# TPS65133_SingleChannel.net
KiCad netlist of a schematic drawn in Altium Designer
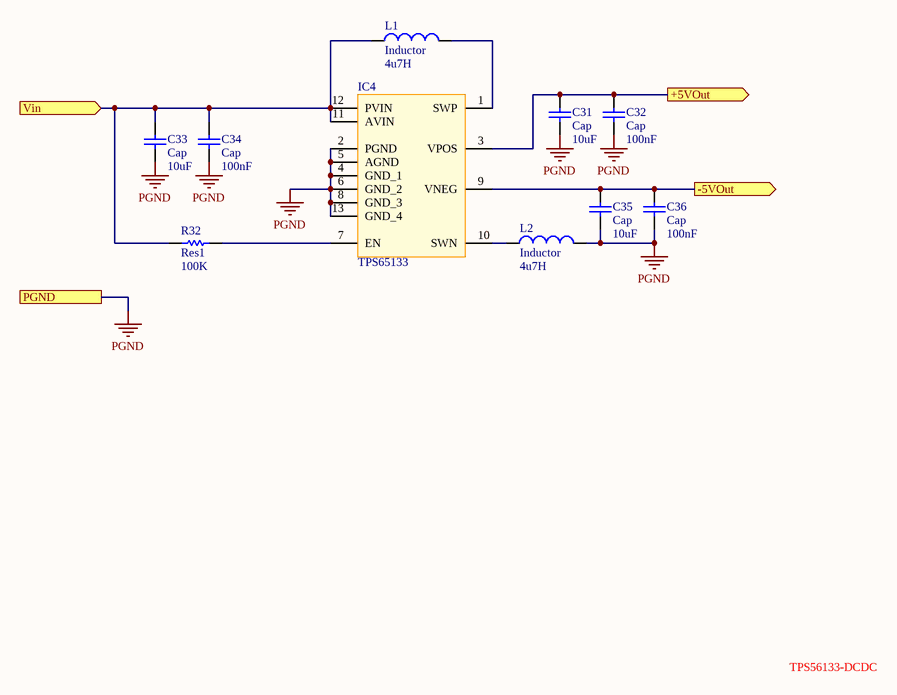
[diagram p0: TPS65133_SingleChannel.SchDoc]

(export (version "E")
  (design (tool "Eeschema 10.0.6"))
  (components
    (comp (ref "C31")
      (value "Cap")
      (footprint "0603C")
      (description "Capacitor")
      (fields (field (name "ALTIUM_VALUE") "10uF") (field (name "PUBLISHER") "Altium Limited"))
      (libsource (lib "Miscellaneous Devices") (part "Cap"))
    )
    (comp (ref "C32")
      (value "Cap")
      (footprint "0603C")
      (description "Capacitor")
      (fields (field (name "ALTIUM_VALUE") "100nF") (field (name "PUBLISHER") "Altium Limited"))
      (libsource (lib "Miscellaneous Devices") (part "Cap"))
    )
    (comp (ref "C33")
      (value "Cap")
      (footprint "0603C")
      (description "Capacitor")
      (fields (field (name "ALTIUM_VALUE") "10uF") (field (name "PUBLISHER") "Altium Limited"))
      (libsource (lib "Miscellaneous Devices") (part "Cap"))
    )
    (comp (ref "C34")
      (value "Cap")
      (footprint "0603C")
      (description "Capacitor")
      (fields (field (name "ALTIUM_VALUE") "100nF") (field (name "PUBLISHER") "Altium Limited"))
      (libsource (lib "Miscellaneous Devices") (part "Cap"))
    )
    (comp (ref "C35")
      (value "Cap")
      (footprint "0603C")
      (description "Capacitor")
      (fields (field (name "ALTIUM_VALUE") "10uF") (field (name "PUBLISHER") "Altium Limited"))
      (libsource (lib "Miscellaneous Devices") (part "Cap"))
    )
    (comp (ref "C36")
      (value "Cap")
      (footprint "0603C")
      (description "Capacitor")
      (fields (field (name "ALTIUM_VALUE") "100nF") (field (name "PUBLISHER") "Altium Limited"))
      (libsource (lib "Miscellaneous Devices") (part "Cap"))
    )
    (comp (ref "IC4")
      (value "TPS65133")
      (footprint "脉诊:SON45P300X300X80-13N-D")
      (description "±5V，250mA 双输出DC-DC电源")
      (fields
        (field (name "MANUFACTURER_PART_NUMBER") "TPS65133DPDR")
        (field (name "MOUSER PART NUMBER") "595-TPS65133DPDR")
      )
      (libsource (lib "脉诊") (part "TPS65133DPDR"))
    )
    (comp (ref "L1")
      (value "Inductor")
      (footprint "0402-A")
      (fields (field (name "ALTIUM_VALUE") "4u7H") (field (name "PUBLISHER") "Altium Limited"))
      (libsource (lib "Miscellaneous Devices") (part "Inductor"))
    )
    (comp (ref "L2")
      (value "Inductor")
      (footprint "0402-A")
      (fields (field (name "ALTIUM_VALUE") "4u7H") (field (name "PUBLISHER") "Altium Limited"))
      (libsource (lib "Miscellaneous Devices") (part "Inductor"))
    )
    (comp (ref "R32")
      (value "Res1")
      (footprint "0603R")
      (description "Resistor")
      (fields (field (name "ALTIUM_VALUE") "100K") (field (name "PUBLISHER") "Altium Limited"))
      (libsource (lib "Miscellaneous Devices") (part "Res1"))
    )
  )
  (nets
    (net (code "1") (name "/+5VOut") (class "Default")
      (node (ref "C31") (pin "2") (pinfunction "2_2") (pintype "passive"))
      (node (ref "C32") (pin "2") (pinfunction "2_2") (pintype "passive"))
      (node (ref "IC4") (pin "3") (pinfunction "VPOS_3") (pintype "passive"))
    )
    (net (code "2") (name "/-5VOut") (class "Default")
      (node (ref "C35") (pin "2") (pinfunction "2_2") (pintype "passive"))
      (node (ref "C36") (pin "2") (pinfunction "2_2") (pintype "passive"))
      (node (ref "IC4") (pin "9") (pinfunction "VNEG_9") (pintype "passive"))
    )
    (net (code "3") (name "/Vin") (class "Default")
      (node (ref "C33") (pin "2") (pinfunction "2_2") (pintype "passive"))
      (node (ref "C34") (pin "2") (pinfunction "2_2") (pintype "passive"))
      (node (ref "IC4") (pin "11") (pinfunction "AVIN_11") (pintype "passive"))
      (node (ref "IC4") (pin "12") (pinfunction "PVIN_12") (pintype "passive"))
      (node (ref "L1") (pin "1") (pinfunction "1_1") (pintype "passive"))
      (node (ref "R32") (pin "1") (pinfunction "1_1") (pintype "passive"))
    )
    (net (code "4") (name "Net-(IC4-EN)") (class "Default")
      (node (ref "IC4") (pin "7") (pinfunction "EN_7") (pintype "passive"))
      (node (ref "R32") (pin "2") (pinfunction "2_2") (pintype "passive"))
    )
    (net (code "5") (name "Net-(IC4-SWN)") (class "Default")
      (node (ref "IC4") (pin "10") (pinfunction "SWN_10") (pintype "passive"))
      (node (ref "L2") (pin "1") (pinfunction "1_1") (pintype "passive"))
    )
    (net (code "6") (name "Net-(IC4-SWP)") (class "Default")
      (node (ref "IC4") (pin "1") (pinfunction "SWP_1") (pintype "passive"))
      (node (ref "L1") (pin "2") (pinfunction "2_2") (pintype "passive"))
    )
    (net (code "7") (name "PGND") (class "Default")
      (node (ref "C31") (pin "1") (pinfunction "1_1") (pintype "passive"))
      (node (ref "C32") (pin "1") (pinfunction "1_1") (pintype "passive"))
      (node (ref "C33") (pin "1") (pinfunction "1_1") (pintype "passive"))
      (node (ref "C34") (pin "1") (pinfunction "1_1") (pintype "passive"))
      (node (ref "C35") (pin "1") (pinfunction "1_1") (pintype "passive"))
      (node (ref "C36") (pin "1") (pinfunction "1_1") (pintype "passive"))
      (node (ref "IC4") (pin "13") (pinfunction "GND_4_13") (pintype "passive"))
      (node (ref "IC4") (pin "2") (pinfunction "PGND_2") (pintype "passive"))
      (node (ref "IC4") (pin "4") (pinfunction "GND_1_4") (pintype "passive"))
      (node (ref "IC4") (pin "5") (pinfunction "AGND_5") (pintype "passive"))
      (node (ref "IC4") (pin "6") (pinfunction "GND_2_6") (pintype "passive"))
      (node (ref "IC4") (pin "8") (pinfunction "GND_3_8") (pintype "passive"))
      (node (ref "L2") (pin "2") (pinfunction "2_2") (pintype "passive"))
    )
  )
)
